# 611_jetbot_124.net
KiCad netlist of a schematic drawn in EAGLE
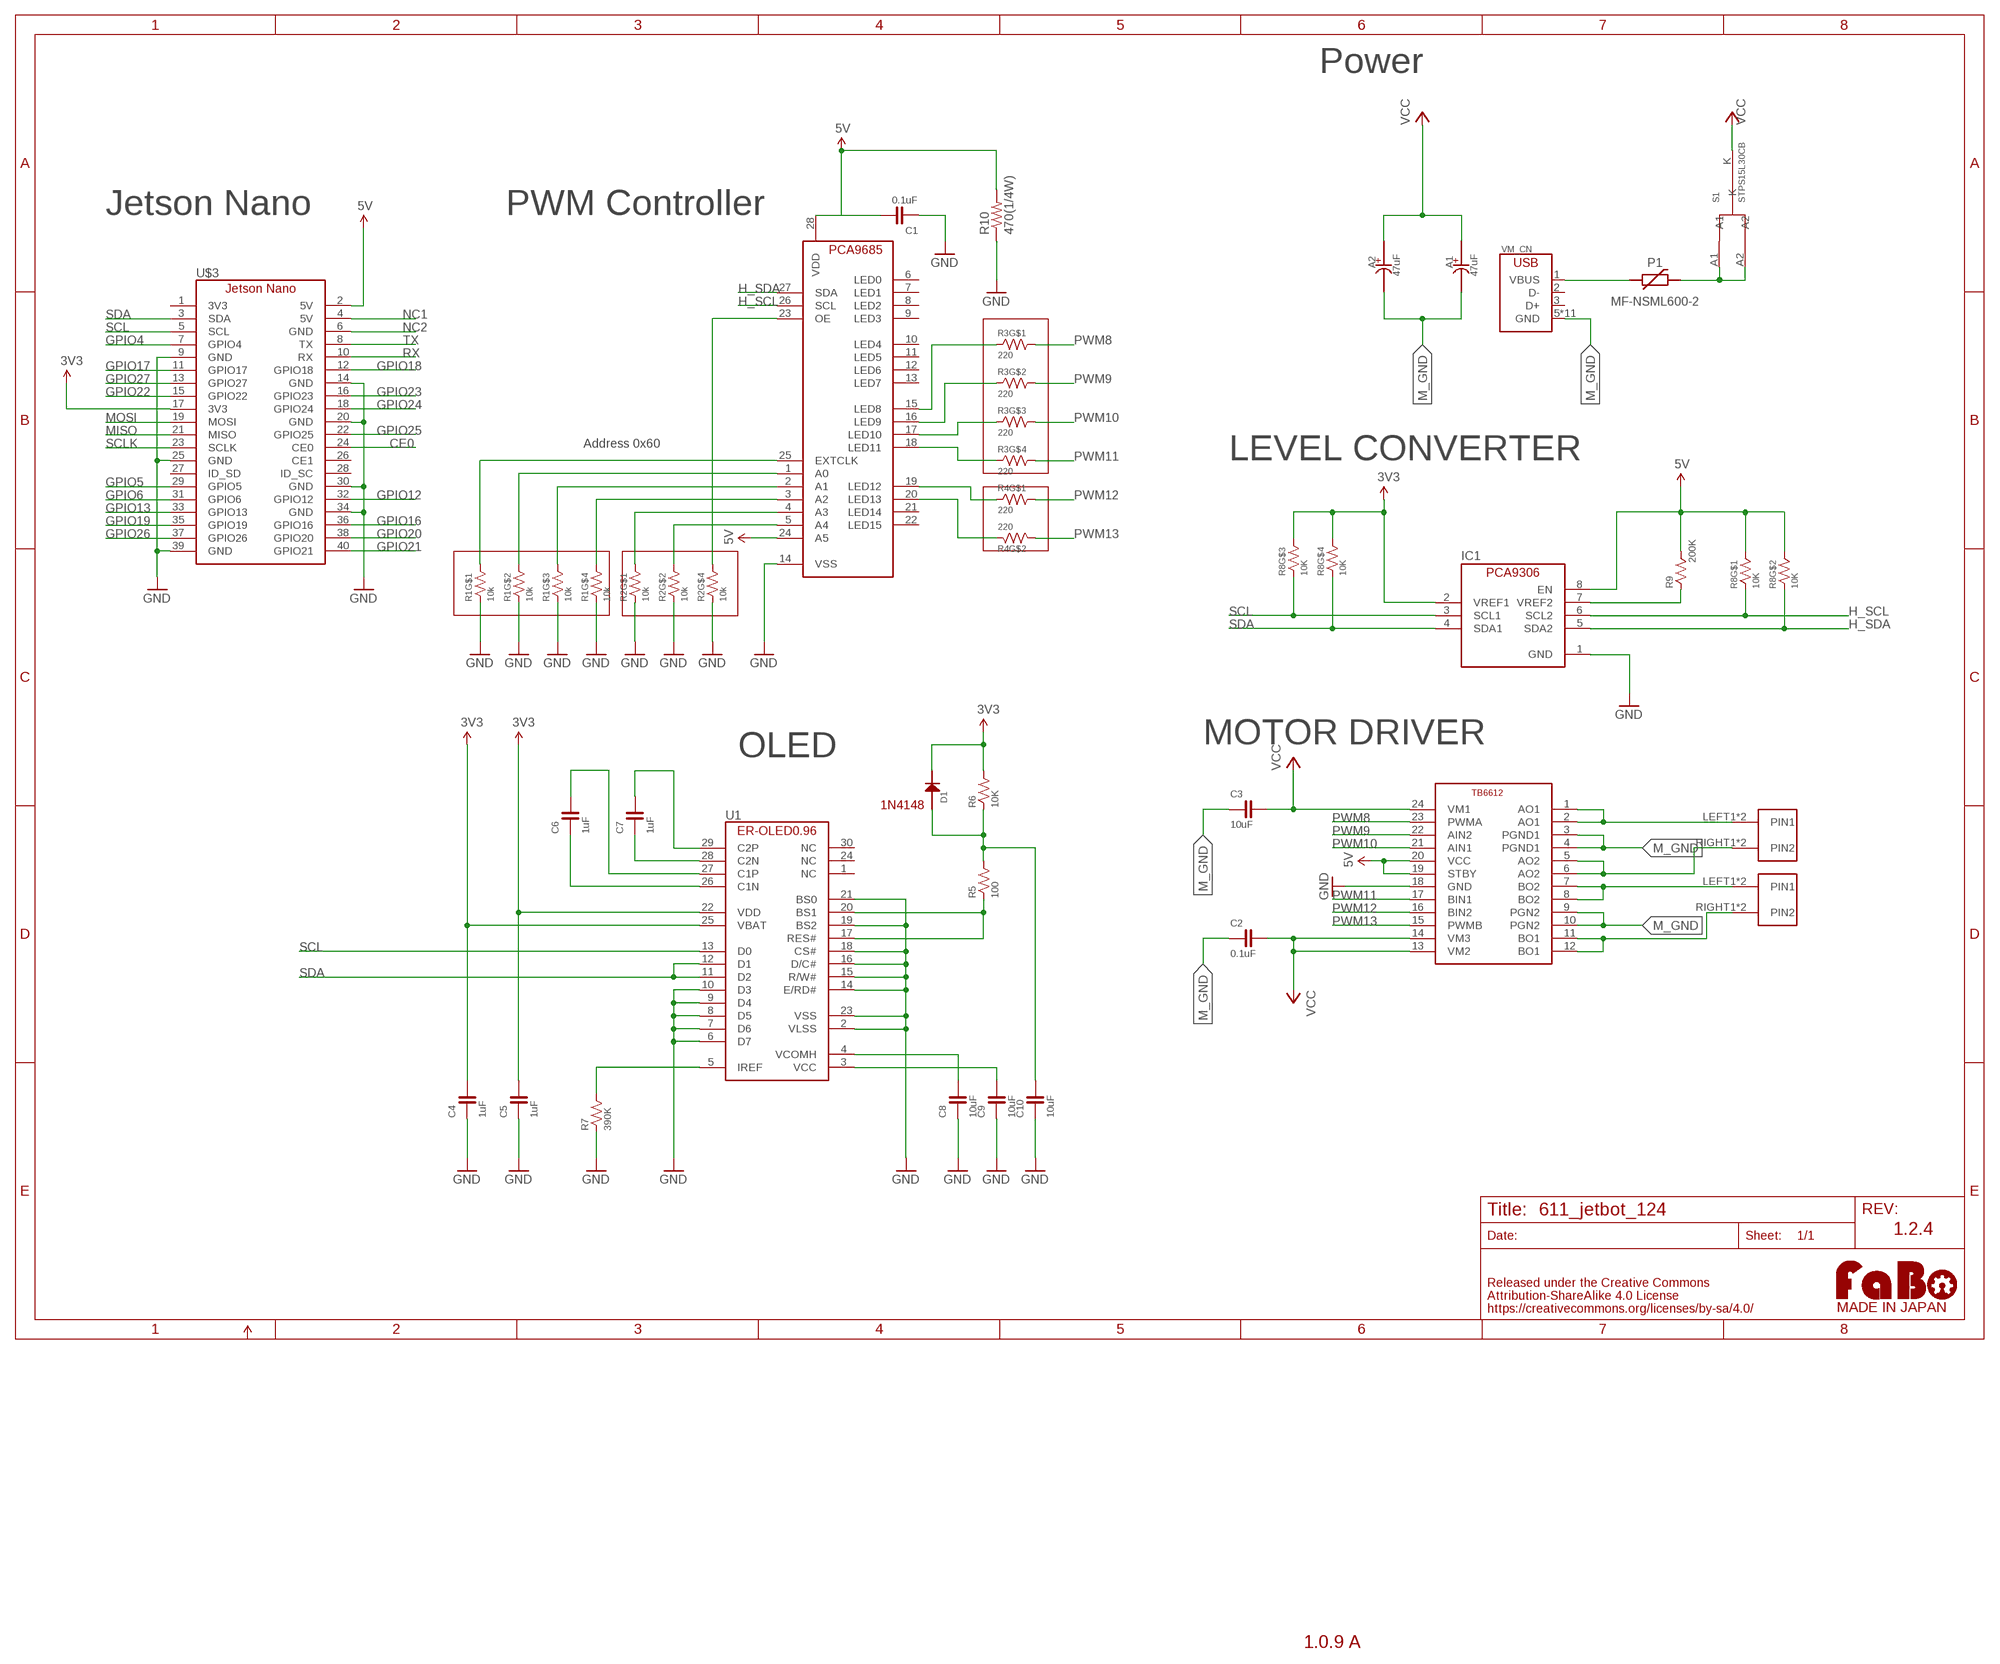
[diagram p0: schematic, sheet 1]

(export (version "E")
  (design (tool "Eeschema 10.0.6"))
  (components
    (comp (ref "A1")
      (value "47uF")
      (footprint "eagle-import:D60")
      (libsource (lib "eagle-import") (part "CAPACITOR-ALUMIN_D60"))
    )
    (comp (ref "A2")
      (value "47uF")
      (footprint "eagle-import:D60")
      (libsource (lib "eagle-import") (part "CAPACITOR-ALUMIN_D60"))
    )
    (comp (ref "C1")
      (value "0.1uF")
      (footprint "eagle-import:0603")
      (libsource (lib "eagle-import") (part "CAPACITOR-0603"))
    )
    (comp (ref "C2")
      (value "0.1uF")
      (footprint "eagle-import:0603")
      (libsource (lib "eagle-import") (part "CAPACITOR-0603"))
    )
    (comp (ref "C3")
      (value "10uF")
      (footprint "eagle-import:0603")
      (libsource (lib "eagle-import") (part "CAPACITOR-0603"))
    )
    (comp (ref "C4")
      (value "1uF")
      (footprint "eagle-import:0603-BOTTOM")
      (libsource (lib "eagle-import") (part "CAPACITOR-0603-BOTTOM"))
    )
    (comp (ref "C5")
      (value "1uF")
      (footprint "eagle-import:0603-BOTTOM")
      (libsource (lib "eagle-import") (part "CAPACITOR-0603-BOTTOM"))
    )
    (comp (ref "C6")
      (value "1uF")
      (footprint "eagle-import:0603-BOTTOM")
      (libsource (lib "eagle-import") (part "CAPACITOR-0603-BOTTOM"))
    )
    (comp (ref "C7")
      (value "1uF")
      (footprint "eagle-import:0603-BOTTOM")
      (libsource (lib "eagle-import") (part "CAPACITOR-0603-BOTTOM"))
    )
    (comp (ref "C8")
      (value "10uF")
      (footprint "eagle-import:0603-BOTTOM")
      (libsource (lib "eagle-import") (part "CAPACITOR-0603-BOTTOM"))
    )
    (comp (ref "C9")
      (value "10uF")
      (footprint "eagle-import:0603-BOTTOM")
      (libsource (lib "eagle-import") (part "CAPACITOR-0603-BOTTOM"))
    )
    (comp (ref "C10")
      (value "10uF")
      (footprint "eagle-import:0603-BOTTOM")
      (libsource (lib "eagle-import") (part "CAPACITOR-0603-BOTTOM"))
    )
    (comp (ref "D1")
      (value "1N4148")
      (footprint "eagle-import:1N4148W")
      (libsource (lib "eagle-import") (part "1N4148"))
    )
    (comp (ref "IC1")
      (value "PCA9306_SSOP")
      (footprint "eagle-import:8PIN-SSOP")
      (libsource (lib "eagle-import") (part "PCA9306_SSOP"))
    )
    (comp (ref "P1")
      (value "MF-NSML600-2")
      (footprint "eagle-import:1206")
      (libsource (lib "eagle-import") (part "POLYSWITCH1206"))
    )
    (comp (ref "R1")
      (value "10k")
      (footprint "eagle-import:EXBV8V")
      (libsource (lib "eagle-import") (part "RESISTOR_ARRAY"))
    )
    (comp (ref "R2")
      (value "10k")
      (footprint "eagle-import:EXBV8V")
      (libsource (lib "eagle-import") (part "RESISTOR_ARRAY"))
    )
    (comp (ref "R3")
      (value "220")
      (footprint "eagle-import:EXBV8V")
      (libsource (lib "eagle-import") (part "RESISTOR_ARRAY"))
    )
    (comp (ref "R4")
      (value "220")
      (footprint "eagle-import:EXBV8V")
      (libsource (lib "eagle-import") (part "RESISTOR_ARRAY"))
    )
    (comp (ref "R5")
      (value "100")
      (footprint "eagle-import:0603-BOTTOM")
      (libsource (lib "eagle-import") (part "RESISTOR-0603-BOTTOM"))
    )
    (comp (ref "R6")
      (value "10K")
      (footprint "eagle-import:0603-BOTTOM")
      (libsource (lib "eagle-import") (part "RESISTOR-0603-BOTTOM"))
    )
    (comp (ref "R7")
      (value "390K")
      (footprint "eagle-import:0603-BOTTOM")
      (libsource (lib "eagle-import") (part "RESISTOR-0603-BOTTOM"))
    )
    (comp (ref "R8")
      (value "10K")
      (footprint "eagle-import:EXBV8V")
      (libsource (lib "eagle-import") (part "RESISTOR_ARRAY"))
    )
    (comp (ref "R9")
      (value "200K")
      (footprint "eagle-import:0603")
      (libsource (lib "eagle-import") (part "RESISTOR-0603"))
    )
    (comp (ref "R10")
      (value "470(1/4W)")
      (footprint "eagle-import:R3216W")
      (libsource (lib "eagle-import") (part "R-US_R3216W"))
    )
    (comp (ref "S1")
      (value "STPS15L30CB")
      (footprint "eagle-import:STPS15L30C")
      (libsource (lib "eagle-import") (part "STPS15L30C"))
    )
    (comp (ref "U$3")
      (value "JETSON_NANO")
      (footprint "eagle-import:JETSON_NANO")
      (libsource (lib "eagle-import") (part "JETSON_NANO"))
    )
    (comp (ref "U$5")
      (value "TB6612")
      (footprint "eagle-import:TB6612")
      (libsource (lib "eagle-import") (part "TB6612"))
    )
    (comp (ref "U$6")
      (value "ML-1400-S1")
      (footprint "eagle-import:ML-1400-S1")
      (libsource (lib "eagle-import") (part "ML-1400-S1"))
    )
    (comp (ref "U$8")
      (value "ML-1400-S1")
      (footprint "eagle-import:ML-1400-S1")
      (libsource (lib "eagle-import") (part "ML-1400-S1"))
    )
    (comp (ref "U$9")
      (value "PCA9685")
      (footprint "eagle-import:PCA9685")
      (libsource (lib "eagle-import") (part "PCA9685"))
    )
    (comp (ref "U$14")
      (value "LOGO_FABO-M")
      (footprint "eagle-import:LOGO_FABO_MS")
      (libsource (lib "eagle-import") (part "LOGO_FABO-M"))
    )
    (comp (ref "U1")
      (value "ER-OLED0.96-1ER-CON30HT-1")
      (footprint "eagle-import:ER-CON30HT-1")
      (libsource (lib "eagle-import") (part "ER-OLED0.96-1ER-CON30HT-1"))
    )
    (comp (ref "VM_CN")
      (value "USB-ZX62D")
      (footprint "eagle-import:ZX62D-B-5PA8")
      (libsource (lib "eagle-import") (part "USB-ZX62D"))
    )
  )
  (nets
    (net (code "1") (name "/CE0") (class "Default")
      (node (ref "U$3") (pin "24") (pinfunction "CE0_24") (pintype "bidirectional"))
    )
    (net (code "2") (name "/GPIO4") (class "Default")
      (node (ref "U$3") (pin "7") (pinfunction "GPIO4_7") (pintype "bidirectional"))
    )
    (net (code "3") (name "/GPIO5") (class "Default")
      (node (ref "U$3") (pin "29") (pinfunction "GPIO5_29") (pintype "bidirectional"))
    )
    (net (code "4") (name "/GPIO6") (class "Default")
      (node (ref "U$3") (pin "31") (pinfunction "GPIO6_31") (pintype "bidirectional"))
    )
    (net (code "5") (name "/GPIO12") (class "Default")
      (node (ref "U$3") (pin "32") (pinfunction "GPIO12_32") (pintype "bidirectional"))
    )
    (net (code "6") (name "/GPIO13") (class "Default")
      (node (ref "U$3") (pin "33") (pinfunction "GPIO13_33") (pintype "bidirectional"))
    )
    (net (code "7") (name "/GPIO16") (class "Default")
      (node (ref "U$3") (pin "36") (pinfunction "GPIO16_36") (pintype "bidirectional"))
    )
    (net (code "8") (name "/GPIO17") (class "Default")
      (node (ref "U$3") (pin "11") (pinfunction "GPIO17_11") (pintype "bidirectional"))
    )
    (net (code "9") (name "/GPIO18") (class "Default")
      (node (ref "U$3") (pin "12") (pinfunction "GPIO18_12") (pintype "bidirectional"))
    )
    (net (code "10") (name "/GPIO19") (class "Default")
      (node (ref "U$3") (pin "35") (pinfunction "GPIO19_35") (pintype "bidirectional"))
    )
    (net (code "11") (name "/GPIO20") (class "Default")
      (node (ref "U$3") (pin "38") (pinfunction "GPIO20_38") (pintype "bidirectional"))
    )
    (net (code "12") (name "/GPIO21") (class "Default")
      (node (ref "U$3") (pin "40") (pinfunction "GPIO21_40") (pintype "bidirectional"))
    )
    (net (code "13") (name "/GPIO22") (class "Default")
      (node (ref "U$3") (pin "15") (pinfunction "GPIO22_15") (pintype "bidirectional"))
    )
    (net (code "14") (name "/GPIO23") (class "Default")
      (node (ref "U$3") (pin "16") (pinfunction "GPIO23_16") (pintype "bidirectional"))
    )
    (net (code "15") (name "/GPIO24") (class "Default")
      (node (ref "U$3") (pin "18") (pinfunction "GPIO24_18") (pintype "bidirectional"))
    )
    (net (code "16") (name "/GPIO25") (class "Default")
      (node (ref "U$3") (pin "22") (pinfunction "GPIO25_22") (pintype "bidirectional"))
    )
    (net (code "17") (name "/GPIO26") (class "Default")
      (node (ref "U$3") (pin "37") (pinfunction "GPIO26_37") (pintype "bidirectional"))
    )
    (net (code "18") (name "/GPIO27") (class "Default")
      (node (ref "U$3") (pin "13") (pinfunction "GPIO27_13") (pintype "bidirectional"))
    )
    (net (code "19") (name "/H_SCL") (class "Default")
      (node (ref "IC1") (pin "6") (pinfunction "SCL2_6") (pintype "bidirectional"))
      (node (ref "R8") (pin "1") (pinfunction "1_1") (pintype "bidirectional"))
      (node (ref "U$9") (pin "26") (pinfunction "SCL_26") (pintype "bidirectional"))
    )
    (net (code "20") (name "/H_SDA") (class "Default")
      (node (ref "IC1") (pin "5") (pinfunction "SDA2_5") (pintype "bidirectional"))
      (node (ref "R8") (pin "2") (pinfunction "1_2") (pintype "bidirectional"))
      (node (ref "U$9") (pin "27") (pinfunction "SDA_27") (pintype "bidirectional"))
    )
    (net (code "21") (name "/MISO") (class "Default")
      (node (ref "U$3") (pin "21") (pinfunction "MISO_21") (pintype "bidirectional"))
    )
    (net (code "22") (name "/MOSI") (class "Default")
      (node (ref "U$3") (pin "19") (pinfunction "MOSI_19") (pintype "bidirectional"))
    )
    (net (code "23") (name "/NC1") (class "Default")
      (node (ref "U$3") (pin "4") (pinfunction "5V_4") (pintype "bidirectional"))
    )
    (net (code "24") (name "/NC2") (class "Default")
      (node (ref "U$3") (pin "6") (pinfunction "GND_6") (pintype "bidirectional"))
    )
    (net (code "25") (name "/PWM8") (class "Default")
      (node (ref "R3") (pin "8") (pinfunction "2_8") (pintype "bidirectional"))
      (node (ref "U$5") (pin "23") (pinfunction "PWMA_23") (pintype "bidirectional"))
    )
    (net (code "26") (name "/PWM9") (class "Default")
      (node (ref "R3") (pin "7") (pinfunction "2_7") (pintype "bidirectional"))
      (node (ref "U$5") (pin "22") (pinfunction "AIN2_22") (pintype "bidirectional"))
    )
    (net (code "27") (name "/PWM10") (class "Default")
      (node (ref "R3") (pin "6") (pinfunction "2_6") (pintype "bidirectional"))
      (node (ref "U$5") (pin "21") (pinfunction "AIN1_21") (pintype "bidirectional"))
    )
    (net (code "28") (name "/PWM11") (class "Default")
      (node (ref "R3") (pin "5") (pinfunction "2_5") (pintype "bidirectional"))
      (node (ref "U$5") (pin "17") (pinfunction "BIN1_17") (pintype "bidirectional"))
    )
    (net (code "29") (name "/PWM12") (class "Default")
      (node (ref "R4") (pin "8") (pinfunction "2_8") (pintype "bidirectional"))
      (node (ref "U$5") (pin "16") (pinfunction "BIN2_16") (pintype "bidirectional"))
    )
    (net (code "30") (name "/PWM13") (class "Default")
      (node (ref "R4") (pin "7") (pinfunction "2_7") (pintype "bidirectional"))
      (node (ref "U$5") (pin "15") (pinfunction "PWMB_15") (pintype "bidirectional"))
    )
    (net (code "31") (name "/RX") (class "Default")
      (node (ref "U$3") (pin "10") (pinfunction "RX_10") (pintype "bidirectional"))
    )
    (net (code "32") (name "/SCL") (class "Default")
      (node (ref "IC1") (pin "3") (pinfunction "SCL1_3") (pintype "bidirectional"))
      (node (ref "R8") (pin "3") (pinfunction "1_3") (pintype "bidirectional"))
      (node (ref "U$3") (pin "5") (pinfunction "SCL_5") (pintype "bidirectional"))
      (node (ref "U1") (pin "13") (pinfunction "D0_13") (pintype "bidirectional"))
    )
    (net (code "33") (name "/SCLK") (class "Default")
      (node (ref "U$3") (pin "23") (pinfunction "SCLK_23") (pintype "bidirectional"))
    )
    (net (code "34") (name "/SDA") (class "Default")
      (node (ref "IC1") (pin "4") (pinfunction "SDA1_4") (pintype "bidirectional"))
      (node (ref "R8") (pin "4") (pinfunction "1_4") (pintype "bidirectional"))
      (node (ref "U$3") (pin "3") (pinfunction "SDA_3") (pintype "bidirectional"))
      (node (ref "U1") (pin "11") (pinfunction "D2_11") (pintype "bidirectional"))
      (node (ref "U1") (pin "12") (pinfunction "D1_12") (pintype "bidirectional"))
    )
    (net (code "35") (name "/TX") (class "Default")
      (node (ref "U$3") (pin "8") (pinfunction "TX_8") (pintype "bidirectional"))
    )
    (net (code "36") (name "3V3") (class "Default")
      (node (ref "C4") (pin "2") (pinfunction "2_2") (pintype "passive"))
      (node (ref "C5") (pin "2") (pinfunction "2_2") (pintype "passive"))
      (node (ref "D1") (pin "CATHODE") (pinfunction "CATHODE_CATHODE") (pintype "bidirectional"))
      (node (ref "IC1") (pin "2") (pinfunction "VREF1_2") (pintype "bidirectional"))
      (node (ref "R6") (pin "2") (pinfunction "2_2") (pintype "bidirectional"))
      (node (ref "R8") (pin "5") (pinfunction "2_5") (pintype "bidirectional"))
      (node (ref "R8") (pin "6") (pinfunction "2_6") (pintype "bidirectional"))
      (node (ref "U$3") (pin "17") (pinfunction "3V3_17") (pintype "bidirectional"))
      (node (ref "U1") (pin "22") (pinfunction "VDD_22") (pintype "bidirectional"))
      (node (ref "U1") (pin "25") (pinfunction "VBAT_25") (pintype "bidirectional"))
    )
    (net (code "37") (name "5V") (class "Default")
      (node (ref "C1") (pin "2") (pinfunction "2_2") (pintype "passive"))
      (node (ref "IC1") (pin "8") (pinfunction "EN_8") (pintype "bidirectional"))
      (node (ref "R10") (pin "2") (pinfunction "2_2") (pintype "passive"))
      (node (ref "R8") (pin "7") (pinfunction "2_7") (pintype "bidirectional"))
      (node (ref "R8") (pin "8") (pinfunction "2_8") (pintype "bidirectional"))
      (node (ref "R9") (pin "2") (pinfunction "2_2") (pintype "bidirectional"))
      (node (ref "U$3") (pin "2") (pinfunction "5V_2") (pintype "bidirectional"))
      (node (ref "U$5") (pin "19") (pinfunction "STBY_19") (pintype "bidirectional"))
      (node (ref "U$5") (pin "20") (pinfunction "VCC_20") (pintype "bidirectional"))
      (node (ref "U$9") (pin "24") (pinfunction "A5_24") (pintype "bidirectional"))
      (node (ref "U$9") (pin "28") (pinfunction "VDD_28") (pintype "bidirectional"))
    )
    (net (code "38") (name "GND") (class "Default")
      (node (ref "C1") (pin "1") (pinfunction "1_1") (pintype "passive"))
      (node (ref "C10") (pin "1") (pinfunction "1_1") (pintype "passive"))
      (node (ref "C4") (pin "1") (pinfunction "1_1") (pintype "passive"))
      (node (ref "C5") (pin "1") (pinfunction "1_1") (pintype "passive"))
      (node (ref "C8") (pin "1") (pinfunction "1_1") (pintype "passive"))
      (node (ref "C9") (pin "1") (pinfunction "1_1") (pintype "passive"))
      (node (ref "IC1") (pin "1") (pinfunction "GND_1") (pintype "bidirectional"))
      (node (ref "R1") (pin "1") (pinfunction "1_1") (pintype "bidirectional"))
      (node (ref "R1") (pin "2") (pinfunction "1_2") (pintype "bidirectional"))
      (node (ref "R1") (pin "3") (pinfunction "1_3") (pintype "bidirectional"))
      (node (ref "R1") (pin "4") (pinfunction "1_4") (pintype "bidirectional"))
      (node (ref "R10") (pin "1") (pinfunction "1_1") (pintype "passive"))
      (node (ref "R2") (pin "1") (pinfunction "1_1") (pintype "bidirectional"))
      (node (ref "R2") (pin "2") (pinfunction "1_2") (pintype "bidirectional"))
      (node (ref "R2") (pin "4") (pinfunction "1_4") (pintype "bidirectional"))
      (node (ref "R7") (pin "1") (pinfunction "1_1") (pintype "bidirectional"))
      (node (ref "U$3") (pin "14") (pinfunction "GND_14") (pintype "bidirectional"))
      (node (ref "U$3") (pin "20") (pinfunction "GND_20") (pintype "bidirectional"))
      (node (ref "U$3") (pin "25") (pinfunction "GND_25") (pintype "bidirectional"))
      (node (ref "U$3") (pin "30") (pinfunction "GND_30") (pintype "bidirectional"))
      (node (ref "U$3") (pin "34") (pinfunction "GND_34") (pintype "bidirectional"))
      (node (ref "U$3") (pin "39") (pinfunction "GND_39") (pintype "bidirectional"))
      (node (ref "U$3") (pin "9") (pinfunction "GND_9") (pintype "bidirectional"))
      (node (ref "U$5") (pin "18") (pinfunction "GND_18") (pintype "bidirectional"))
      (node (ref "U$9") (pin "14") (pinfunction "VSS_14") (pintype "bidirectional"))
      (node (ref "U1") (pin "10") (pinfunction "D3_10") (pintype "bidirectional"))
      (node (ref "U1") (pin "14") (pinfunction "E/RD#_14") (pintype "bidirectional"))
      (node (ref "U1") (pin "15") (pinfunction "R/W#_15") (pintype "bidirectional"))
      (node (ref "U1") (pin "16") (pinfunction "D/C#_16") (pintype "bidirectional"))
      (node (ref "U1") (pin "18") (pinfunction "CS#_18") (pintype "bidirectional"))
      (node (ref "U1") (pin "19") (pinfunction "BS2_19") (pintype "bidirectional"))
      (node (ref "U1") (pin "2") (pinfunction "VLSS_2") (pintype "bidirectional"))
      (node (ref "U1") (pin "21") (pinfunction "BS0_21") (pintype "bidirectional"))
      (node (ref "U1") (pin "23") (pinfunction "VSS_23") (pintype "bidirectional"))
      (node (ref "U1") (pin "6") (pinfunction "D7_6") (pintype "bidirectional"))
      (node (ref "U1") (pin "7") (pinfunction "D6_7") (pintype "bidirectional"))
      (node (ref "U1") (pin "8") (pinfunction "D5_8") (pintype "bidirectional"))
      (node (ref "U1") (pin "9") (pinfunction "D4_9") (pintype "bidirectional"))
    )
    (net (code "39") (name "M_GND") (class "Default")
      (node (ref "A1") (pin "MINUS") (pinfunction "-_MINUS") (pintype "passive"))
      (node (ref "A2") (pin "MINUS") (pinfunction "-_MINUS") (pintype "passive"))
      (node (ref "C2") (pin "1") (pinfunction "1_1") (pintype "passive"))
      (node (ref "C3") (pin "1") (pinfunction "1_1") (pintype "passive"))
      (node (ref "U$5") (pin "10") (pinfunction "PGN2_10") (pintype "bidirectional"))
      (node (ref "U$5") (pin "3") (pinfunction "PGND1_3") (pintype "bidirectional"))
      (node (ref "U$5") (pin "4") (pinfunction "PGND1_4") (pintype "bidirectional"))
      (node (ref "U$5") (pin "9") (pinfunction "PGN2_9") (pintype "bidirectional"))
      (node (ref "VM_CN") (pin "5") (pinfunction "GND_5") (pintype "bidirectional"))
      (node (ref "VM_CN") (pin "B1") (pinfunction "GND_B1") (pintype "bidirectional"))
      (node (ref "VM_CN") (pin "B2") (pinfunction "GND_B2") (pintype "bidirectional"))
      (node (ref "VM_CN") (pin "B3") (pinfunction "GND_B3") (pintype "bidirectional"))
      (node (ref "VM_CN") (pin "B4") (pinfunction "GND_B4") (pintype "bidirectional"))
      (node (ref "VM_CN") (pin "T1") (pinfunction "GND_T1") (pintype "bidirectional"))
      (node (ref "VM_CN") (pin "T2") (pinfunction "GND_T2") (pintype "bidirectional"))
      (node (ref "VM_CN") (pin "T3") (pinfunction "GND_T3") (pintype "bidirectional"))
      (node (ref "VM_CN") (pin "T4") (pinfunction "GND_T4") (pintype "bidirectional"))
      (node (ref "VM_CN") (pin "T5") (pinfunction "GND_T5") (pintype "bidirectional"))
      (node (ref "VM_CN") (pin "T6") (pinfunction "GND_T6") (pintype "bidirectional"))
    )
    (net (code "40") (name "Net-(C10-Pad2)") (class "Default")
      (node (ref "C10") (pin "2") (pinfunction "2_2") (pintype "passive"))
      (node (ref "D1") (pin "ANODE") (pinfunction "ANODE_ANODE") (pintype "bidirectional"))
      (node (ref "R5") (pin "2") (pinfunction "2_2") (pintype "bidirectional"))
      (node (ref "R6") (pin "1") (pinfunction "1_1") (pintype "bidirectional"))
    )
    (net (code "41") (name "Net-(IC1-VREF2)") (class "Default")
      (node (ref "IC1") (pin "7") (pinfunction "VREF2_7") (pintype "bidirectional"))
      (node (ref "R9") (pin "1") (pinfunction "1_1") (pintype "bidirectional"))
    )
    (net (code "42") (name "Net-(P1-1)") (class "Default")
      (node (ref "P1") (pin "P$1") (pinfunction "1_P$1") (pintype "bidirectional"))
      (node (ref "VM_CN") (pin "1") (pinfunction "VBUS_1") (pintype "bidirectional"))
    )
    (net (code "43") (name "Net-(P1-2)") (class "Default")
      (node (ref "P1") (pin "P$2") (pinfunction "2_P$2") (pintype "bidirectional"))
      (node (ref "S1") (pin "A1") (pinfunction "A1_A1") (pintype "bidirectional"))
      (node (ref "S1") (pin "A2") (pinfunction "A2_A2") (pintype "bidirectional"))
    )
    (net (code "44") (name "Net-(R1A-2)") (class "Default")
      (node (ref "R1") (pin "8") (pinfunction "2_8") (pintype "bidirectional"))
      (node (ref "U$9") (pin "25") (pinfunction "EXTCLK_25") (pintype "bidirectional"))
    )
    (net (code "45") (name "Net-(R1B-2)") (class "Default")
      (node (ref "R1") (pin "7") (pinfunction "2_7") (pintype "bidirectional"))
      (node (ref "U$9") (pin "1") (pinfunction "A0_1") (pintype "bidirectional"))
    )
    (net (code "46") (name "Net-(R1C-2)") (class "Default")
      (node (ref "R1") (pin "6") (pinfunction "2_6") (pintype "bidirectional"))
      (node (ref "U$9") (pin "2") (pinfunction "A1_2") (pintype "bidirectional"))
    )
    (net (code "47") (name "Net-(R1D-2)") (class "Default")
      (node (ref "R1") (pin "5") (pinfunction "2_5") (pintype "bidirectional"))
      (node (ref "U$9") (pin "3") (pinfunction "A2_3") (pintype "bidirectional"))
    )
    (net (code "48") (name "Net-(R2A-2)") (class "Default")
      (node (ref "R2") (pin "8") (pinfunction "2_8") (pintype "bidirectional"))
      (node (ref "U$9") (pin "4") (pinfunction "A3_4") (pintype "bidirectional"))
    )
    (net (code "49") (name "Net-(R2B-2)") (class "Default")
      (node (ref "R2") (pin "7") (pinfunction "2_7") (pintype "bidirectional"))
      (node (ref "U$9") (pin "5") (pinfunction "A4_5") (pintype "bidirectional"))
    )
    (net (code "50") (name "Net-(R2D-2)") (class "Default")
      (node (ref "R2") (pin "5") (pinfunction "2_5") (pintype "bidirectional"))
      (node (ref "U$9") (pin "23") (pinfunction "OE_23") (pintype "bidirectional"))
    )
    (net (code "51") (name "Net-(R3B-1)") (class "Default")
      (node (ref "R3") (pin "2") (pinfunction "1_2") (pintype "bidirectional"))
      (node (ref "U$9") (pin "16") (pinfunction "LED9_16") (pintype "bidirectional"))
    )
    (net (code "52") (name "Net-(R3C-1)") (class "Default")
      (node (ref "R3") (pin "3") (pinfunction "1_3") (pintype "bidirectional"))
      (node (ref "U$9") (pin "17") (pinfunction "LED10_17") (pintype "bidirectional"))
    )
    (net (code "53") (name "Net-(R3D-1)") (class "Default")
      (node (ref "R3") (pin "4") (pinfunction "1_4") (pintype "bidirectional"))
      (node (ref "U$9") (pin "18") (pinfunction "LED11_18") (pintype "bidirectional"))
    )
    (net (code "54") (name "Net-(R4B-1)") (class "Default")
      (node (ref "R4") (pin "2") (pinfunction "1_2") (pintype "bidirectional"))
      (node (ref "U$9") (pin "20") (pinfunction "LED13_20") (pintype "bidirectional"))
    )
    (net (code "55") (name "Net-(U$5-AO1-Pad1)") (class "Default")
      (node (ref "U$5") (pin "1") (pinfunction "AO1_1") (pintype "bidirectional"))
      (node (ref "U$5") (pin "2") (pinfunction "AO1_2") (pintype "bidirectional"))
      (node (ref "U$6") (pin "LEFT1") (pinfunction "PIN1_LEFT1") (pintype "bidirectional"))
      (node (ref "U$6") (pin "LEFT2") (pinfunction "PIN1_LEFT2") (pintype "bidirectional"))
    )
    (net (code "56") (name "Net-(U$5-AO2-Pad5)") (class "Default")
      (node (ref "U$5") (pin "5") (pinfunction "AO2_5") (pintype "bidirectional"))
      (node (ref "U$5") (pin "6") (pinfunction "AO2_6") (pintype "bidirectional"))
      (node (ref "U$6") (pin "RIGHT1") (pinfunction "PIN2_RIGHT1") (pintype "bidirectional"))
      (node (ref "U$6") (pin "RIGHT2") (pinfunction "PIN2_RIGHT2") (pintype "bidirectional"))
    )
    (net (code "57") (name "Net-(U$5-BO1-Pad11)") (class "Default")
      (node (ref "U$5") (pin "11") (pinfunction "BO1_11") (pintype "bidirectional"))
      (node (ref "U$5") (pin "12") (pinfunction "BO1_12") (pintype "bidirectional"))
      (node (ref "U$8") (pin "RIGHT1") (pinfunction "PIN2_RIGHT1") (pintype "bidirectional"))
      (node (ref "U$8") (pin "RIGHT2") (pinfunction "PIN2_RIGHT2") (pintype "bidirectional"))
    )
    (net (code "58") (name "Net-(U$5-BO2-Pad7)") (class "Default")
      (node (ref "U$5") (pin "7") (pinfunction "BO2_7") (pintype "bidirectional"))
      (node (ref "U$5") (pin "8") (pinfunction "BO2_8") (pintype "bidirectional"))
      (node (ref "U$8") (pin "LEFT1") (pinfunction "PIN1_LEFT1") (pintype "bidirectional"))
      (node (ref "U$8") (pin "LEFT2") (pinfunction "PIN1_LEFT2") (pintype "bidirectional"))
    )
    (net (code "59") (name "Net-(U$9-LED8)") (class "Default")
      (node (ref "R3") (pin "1") (pinfunction "1_1") (pintype "bidirectional"))
      (node (ref "U$9") (pin "15") (pinfunction "LED8_15") (pintype "bidirectional"))
    )
    (net (code "60") (name "Net-(U$9-LED12)") (class "Default")
      (node (ref "R4") (pin "1") (pinfunction "1_1") (pintype "bidirectional"))
      (node (ref "U$9") (pin "19") (pinfunction "LED12_19") (pintype "bidirectional"))
    )
    (net (code "61") (name "Net-(U1-BS1)") (class "Default")
      (node (ref "R5") (pin "1") (pinfunction "1_1") (pintype "bidirectional"))
      (node (ref "U1") (pin "17") (pinfunction "RES#_17") (pintype "bidirectional"))
      (node (ref "U1") (pin "20") (pinfunction "BS1_20") (pintype "bidirectional"))
    )
    (net (code "62") (name "Net-(U1-C1N)") (class "Default")
      (node (ref "C6") (pin "1") (pinfunction "1_1") (pintype "passive"))
      (node (ref "U1") (pin "26") (pinfunction "C1N_26") (pintype "bidirectional"))
    )
    (net (code "63") (name "Net-(U1-C1P)") (class "Default")
      (node (ref "C6") (pin "2") (pinfunction "2_2") (pintype "passive"))
      (node (ref "U1") (pin "27") (pinfunction "C1P_27") (pintype "bidirectional"))
    )
    (net (code "64") (name "Net-(U1-C2N)") (class "Default")
      (node (ref "C7") (pin "1") (pinfunction "1_1") (pintype "passive"))
      (node (ref "U1") (pin "28") (pinfunction "C2N_28") (pintype "bidirectional"))
    )
    (net (code "65") (name "Net-(U1-C2P)") (class "Default")
      (node (ref "C7") (pin "2") (pinfunction "2_2") (pintype "passive"))
      (node (ref "U1") (pin "29") (pinfunction "C2P_29") (pintype "bidirectional"))
    )
    (net (code "66") (name "Net-(U1-IREF)") (class "Default")
      (node (ref "R7") (pin "2") (pinfunction "2_2") (pintype "bidirectional"))
      (node (ref "U1") (pin "5") (pinfunction "IREF_5") (pintype "bidirectional"))
    )
    (net (code "67") (name "Net-(U1-VCC)") (class "Default")
      (node (ref "C9") (pin "2") (pinfunction "2_2") (pintype "passive"))
      (node (ref "U1") (pin "3") (pinfunction "VCC_3") (pintype "bidirectional"))
    )
    (net (code "68") (name "Net-(U1-VCOMH)") (class "Default")
      (node (ref "C8") (pin "2") (pinfunction "2_2") (pintype "passive"))
      (node (ref "U1") (pin "4") (pinfunction "VCOMH_4") (pintype "bidirectional"))
    )
    (net (code "69") (name "VCC") (class "Default")
      (node (ref "A1") (pin "PLUS") (pinfunction "+_PLUS") (pintype "passive"))
      (node (ref "A2") (pin "PLUS") (pinfunction "+_PLUS") (pintype "passive"))
      (node (ref "C2") (pin "2") (pinfunction "2_2") (pintype "passive"))
      (node (ref "C3") (pin "2") (pinfunction "2_2") (pintype "passive"))
      (node (ref "S1") (pin "K") (pinfunction "K_K") (pintype "bidirectional"))
      (node (ref "U$5") (pin "13") (pinfunction "VM2_13") (pintype "bidirectional"))
      (node (ref "U$5") (pin "14") (pinfunction "VM3_14") (pintype "bidirectional"))
      (node (ref "U$5") (pin "24") (pinfunction "VM1_24") (pintype "bidirectional"))
    )
    (net (code "70") (name "unconnected-(U$3-3V3-Pad1)") (class "Default")
      (node (ref "U$3") (pin "1") (pinfunction "3V3_1") (pintype "bidirectional"))
    )
    (net (code "71") (name "unconnected-(U$3-CE1-Pad26)") (class "Default")
      (node (ref "U$3") (pin "26") (pinfunction "CE1_26") (pintype "bidirectional"))
    )
    (net (code "72") (name "unconnected-(U$3-ID_SC-Pad28)") (class "Default")
      (node (ref "U$3") (pin "28") (pinfunction "ID_SC_28") (pintype "bidirectional"))
    )
    (net (code "73") (name "unconnected-(U$3-ID_SD-Pad27)") (class "Default")
      (node (ref "U$3") (pin "27") (pinfunction "ID_SD_27") (pintype "bidirectional"))
    )
    (net (code "74") (name "unconnected-(U$9-LED0-Pad6)") (class "Default")
      (node (ref "U$9") (pin "6") (pinfunction "LED0_6") (pintype "bidirectional"))
    )
    (net (code "75") (name "unconnected-(U$9-LED1-Pad7)") (class "Default")
      (node (ref "U$9") (pin "7") (pinfunction "LED1_7") (pintype "bidirectional"))
    )
    (net (code "76") (name "unconnected-(U$9-LED2-Pad8)") (class "Default")
      (node (ref "U$9") (pin "8") (pinfunction "LED2_8") (pintype "bidirectional"))
    )
    (net (code "77") (name "unconnected-(U$9-LED3-Pad9)") (class "Default")
      (node (ref "U$9") (pin "9") (pinfunction "LED3_9") (pintype "bidirectional"))
    )
    (net (code "78") (name "unconnected-(U$9-LED4-Pad10)") (class "Default")
      (node (ref "U$9") (pin "10") (pinfunction "LED4_10") (pintype "bidirectional"))
    )
    (net (code "79") (name "unconnected-(U$9-LED5-Pad11)") (class "Default")
      (node (ref "U$9") (pin "11") (pinfunction "LED5_11") (pintype "bidirectional"))
    )
    (net (code "80") (name "unconnected-(U$9-LED6-Pad12)") (class "Default")
      (node (ref "U$9") (pin "12") (pinfunction "LED6_12") (pintype "bidirectional"))
    )
    (net (code "81") (name "unconnected-(U$9-LED7-Pad13)") (class "Default")
      (node (ref "U$9") (pin "13") (pinfunction "LED7_13") (pintype "bidirectional"))
    )
    (net (code "82") (name "unconnected-(U$9-LED14-Pad21)") (class "Default")
      (node (ref "U$9") (pin "21") (pinfunction "LED14_21") (pintype "bidirectional"))
    )
    (net (code "83") (name "unconnected-(U$9-LED15-Pad22)") (class "Default")
      (node (ref "U$9") (pin "22") (pinfunction "LED15_22") (pintype "bidirectional"))
    )
    (net (code "84") (name "unconnected-(U1-NC-Pad1)") (class "Default")
      (node (ref "U1") (pin "1") (pinfunction "NC_1") (pintype "bidirectional"))
    )
    (net (code "85") (name "unconnected-(U1-NC-Pad24)") (class "Default")
      (node (ref "U1") (pin "24") (pinfunction "NC_24") (pintype "bidirectional"))
    )
    (net (code "86") (name "unconnected-(U1-NC-Pad30)") (class "Default")
      (node (ref "U1") (pin "30") (pinfunction "NC_30") (pintype "bidirectional"))
    )
    (net (code "87") (name "unconnected-(VM_CN-D+-Pad3)") (class "Default")
      (node (ref "VM_CN") (pin "3") (pinfunction "D+_3") (pintype "bidirectional"))
    )
    (net (code "88") (name "unconnected-(VM_CN-D--Pad2)") (class "Default")
      (node (ref "VM_CN") (pin "2") (pinfunction "D-_2") (pintype "bidirectional"))
    )
  )
)
